# Clock.net
KiCad netlist of a schematic drawn in EAGLE
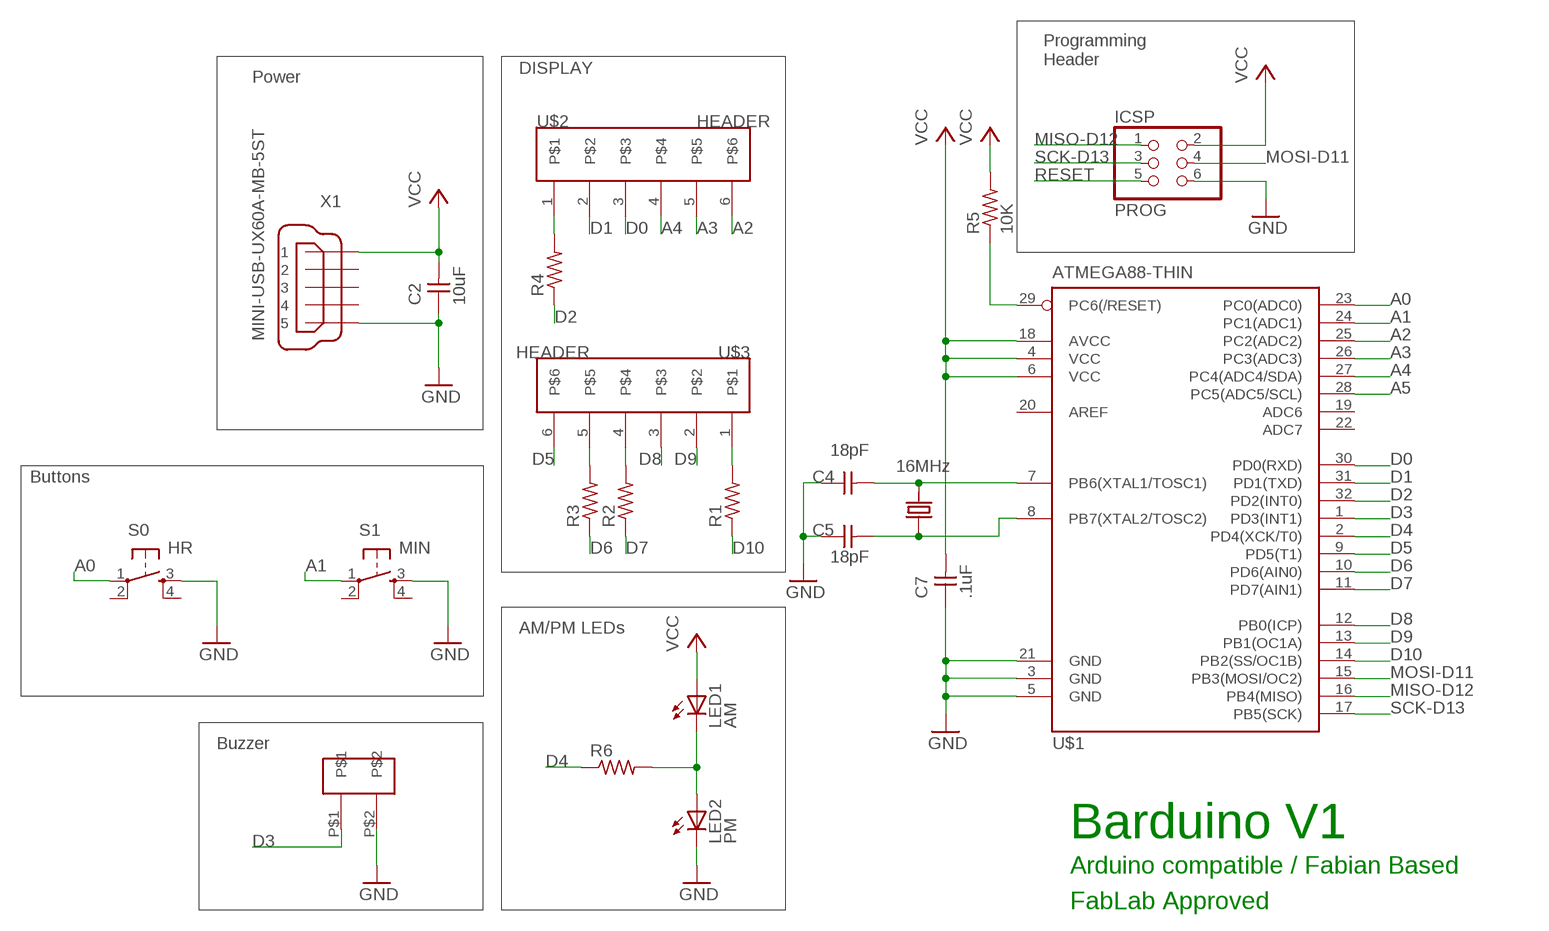
[diagram p0: schematic, sheet 1]

(export (version "E")
  (design (tool "Eeschema 10.0.6"))
  (components
    (comp (ref "C2")
      (value "10uF")
      (footprint "eagle-import:1206")
      (libsource (lib "eagle-import") (part "UNPOLARIZED_CAPACITOR1206"))
    )
    (comp (ref "C4")
      (value "18pF")
      (footprint "eagle-import:1206")
      (libsource (lib "eagle-import") (part "UNPOLARIZED_CAPACITOR1206"))
    )
    (comp (ref "C5")
      (value "18pF")
      (footprint "eagle-import:1206")
      (libsource (lib "eagle-import") (part "UNPOLARIZED_CAPACITOR1206"))
    )
    (comp (ref "C7")
      (value ".1uF")
      (footprint "eagle-import:1206")
      (libsource (lib "eagle-import") (part "UNPOLARIZED_CAPACITOR1206"))
    )
    (comp (ref "ICSP")
      (value "PROG")
      (footprint "eagle-import:2X03SMD")
      (libsource (lib "eagle-import") (part "PINHD-2X3-SMD"))
    )
    (comp (ref "LED1")
      (value "AM")
      (footprint "eagle-import:CHIPLED_1206")
      (libsource (lib "eagle-import") (part "LEDCHIPLED_1206"))
    )
    (comp (ref "LED2")
      (value "PM")
      (footprint "eagle-import:CHIPLED_1206")
      (libsource (lib "eagle-import") (part "LEDCHIPLED_1206"))
    )
    (comp (ref "Q2")
      (value "16MHz")
      (footprint "eagle-import:CS10")
      (libsource (lib "eagle-import") (part "CRYSTALCS10"))
    )
    (comp (ref "R1")
      (value "R-US_R1206")
      (footprint "eagle-import:R1206")
      (libsource (lib "eagle-import") (part "R-US_R1206"))
    )
    (comp (ref "R2")
      (value "R-US_R1206")
      (footprint "eagle-import:R1206")
      (libsource (lib "eagle-import") (part "R-US_R1206"))
    )
    (comp (ref "R3")
      (value "R-US_R1206")
      (footprint "eagle-import:R1206")
      (libsource (lib "eagle-import") (part "R-US_R1206"))
    )
    (comp (ref "R4")
      (value "R-US_R1206")
      (footprint "eagle-import:R1206")
      (libsource (lib "eagle-import") (part "R-US_R1206"))
    )
    (comp (ref "R5")
      (value "10K")
      (footprint "eagle-import:1206")
      (libsource (lib "eagle-import") (part "RESISTOR1206"))
    )
    (comp (ref "R6")
      (value "R-US_R1206")
      (footprint "eagle-import:R1206")
      (libsource (lib "eagle-import") (part "R-US_R1206"))
    )
    (comp (ref "S0")
      (value "HR")
      (footprint "eagle-import:6MM_SWITCH")
      (libsource (lib "eagle-import") (part "6MM_SWITCH6MM_SWITCH"))
    )
    (comp (ref "S1")
      (value "MIN")
      (footprint "eagle-import:6MM_SWITCH")
      (libsource (lib "eagle-import") (part "6MM_SWITCH6MM_SWITCH"))
    )
    (comp (ref "U$1")
      (value "ATMEGA88-THIN")
      (footprint "eagle-import:TQFP32-08THIN")
      (libsource (lib "eagle-import") (part "ATMEGA88-THIN"))
    )
    (comp (ref "U$2")
      (value "HEADER")
      (footprint "eagle-import:HEADER")
      (libsource (lib "eagle-import") (part "HEADER"))
    )
    (comp (ref "U$3")
      (value "HEADER")
      (footprint "eagle-import:HEADER")
      (libsource (lib "eagle-import") (part "HEADER"))
    )
    (comp (ref "U$4")
      (value "BUZZER")
      (footprint "eagle-import:BUZZER")
      (libsource (lib "eagle-import") (part "BUZZER"))
    )
    (comp (ref "X1")
      (value "MINI-USB-UX60A-MB-5ST")
      (footprint "eagle-import:UX60A-MB-5ST")
      (libsource (lib "eagle-import") (part "MINI-USB-UX60A-MB-5ST"))
    )
  )
  (nets
    (net (code "1") (name "/A0") (class "Default")
      (node (ref "S0") (pin "1") (pinfunction "P_1") (pintype "passive"))
      (node (ref "U$1") (pin "23") (pinfunction "PC0(ADC0)_23") (pintype "bidirectional"))
    )
    (net (code "2") (name "/A1") (class "Default")
      (node (ref "S1") (pin "1") (pinfunction "P_1") (pintype "passive"))
      (node (ref "U$1") (pin "24") (pinfunction "PC1(ADC1)_24") (pintype "bidirectional"))
    )
    (net (code "3") (name "/A2") (class "Default")
      (node (ref "U$1") (pin "25") (pinfunction "PC2(ADC2)_25") (pintype "bidirectional"))
      (node (ref "U$2") (pin "6") (pinfunction "P$6_6") (pintype "bidirectional"))
    )
    (net (code "4") (name "/A3") (class "Default")
      (node (ref "U$1") (pin "26") (pinfunction "PC3(ADC3)_26") (pintype "bidirectional"))
      (node (ref "U$2") (pin "5") (pinfunction "P$5_5") (pintype "bidirectional"))
    )
    (net (code "5") (name "/A4") (class "Default")
      (node (ref "U$1") (pin "27") (pinfunction "PC4(ADC4/SDA)_27") (pintype "bidirectional"))
      (node (ref "U$2") (pin "4") (pinfunction "P$4_4") (pintype "bidirectional"))
    )
    (net (code "6") (name "/A5") (class "Default")
      (node (ref "U$1") (pin "28") (pinfunction "PC5(ADC5/SCL)_28") (pintype "bidirectional"))
    )
    (net (code "7") (name "/D0") (class "Default")
      (node (ref "U$1") (pin "30") (pinfunction "PD0(RXD)_30") (pintype "bidirectional"))
      (node (ref "U$2") (pin "3") (pinfunction "P$3_3") (pintype "bidirectional"))
    )
    (net (code "8") (name "/D1") (class "Default")
      (node (ref "U$1") (pin "31") (pinfunction "PD1(TXD)_31") (pintype "bidirectional"))
      (node (ref "U$2") (pin "2") (pinfunction "P$2_2") (pintype "bidirectional"))
    )
    (net (code "9") (name "/D2") (class "Default")
      (node (ref "R4") (pin "1") (pinfunction "1_1") (pintype "passive"))
      (node (ref "U$1") (pin "32") (pinfunction "PD2(INT0)_32") (pintype "bidirectional"))
    )
    (net (code "10") (name "/D3") (class "Default")
      (node (ref "U$1") (pin "1") (pinfunction "PD3(INT1)_1") (pintype "bidirectional"))
      (node (ref "U$4") (pin "P$1") (pinfunction "P$1_P$1") (pintype "bidirectional"))
    )
    (net (code "11") (name "/D4") (class "Default")
      (node (ref "R6") (pin "1") (pinfunction "1_1") (pintype "passive"))
      (node (ref "U$1") (pin "2") (pinfunction "PD4(XCK/T0)_2") (pintype "bidirectional"))
    )
    (net (code "12") (name "/D5") (class "Default")
      (node (ref "U$1") (pin "9") (pinfunction "PD5(T1)_9") (pintype "bidirectional"))
      (node (ref "U$3") (pin "6") (pinfunction "P$6_6") (pintype "bidirectional"))
    )
    (net (code "13") (name "/D6") (class "Default")
      (node (ref "R3") (pin "1") (pinfunction "1_1") (pintype "passive"))
      (node (ref "U$1") (pin "10") (pinfunction "PD6(AIN0)_10") (pintype "bidirectional"))
    )
    (net (code "14") (name "/D7") (class "Default")
      (node (ref "R2") (pin "1") (pinfunction "1_1") (pintype "passive"))
      (node (ref "U$1") (pin "11") (pinfunction "PD7(AIN1)_11") (pintype "bidirectional"))
    )
    (net (code "15") (name "/D8") (class "Default")
      (node (ref "U$1") (pin "12") (pinfunction "PB0(ICP)_12") (pintype "bidirectional"))
      (node (ref "U$3") (pin "3") (pinfunction "P$3_3") (pintype "bidirectional"))
    )
    (net (code "16") (name "/D9") (class "Default")
      (node (ref "U$1") (pin "13") (pinfunction "PB1(OC1A)_13") (pintype "bidirectional"))
      (node (ref "U$3") (pin "2") (pinfunction "P$2_2") (pintype "bidirectional"))
    )
    (net (code "17") (name "/D10") (class "Default")
      (node (ref "R1") (pin "1") (pinfunction "1_1") (pintype "passive"))
      (node (ref "U$1") (pin "14") (pinfunction "PB2(SS/OC1B)_14") (pintype "bidirectional"))
    )
    (net (code "18") (name "/MISO-D12") (class "Default")
      (node (ref "ICSP") (pin "1") (pinfunction "1_1") (pintype "passive"))
      (node (ref "U$1") (pin "16") (pinfunction "PB4(MISO)_16") (pintype "bidirectional"))
    )
    (net (code "19") (name "/MOSI-D11") (class "Default")
      (node (ref "ICSP") (pin "4") (pinfunction "4_4") (pintype "passive"))
      (node (ref "U$1") (pin "15") (pinfunction "PB3(MOSI/OC2)_15") (pintype "bidirectional"))
    )
    (net (code "20") (name "/RESET") (class "Default")
      (node (ref "ICSP") (pin "5") (pinfunction "5_5") (pintype "passive"))
      (node (ref "R5") (pin "1") (pinfunction "1_1") (pintype "passive"))
      (node (ref "U$1") (pin "29") (pinfunction "PC6(/RESET)_29") (pintype "bidirectional"))
    )
    (net (code "21") (name "/SCK-D13") (class "Default")
      (node (ref "ICSP") (pin "3") (pinfunction "3_3") (pintype "passive"))
      (node (ref "U$1") (pin "17") (pinfunction "PB5(SCK)_17") (pintype "bidirectional"))
    )
    (net (code "22") (name "GND") (class "Default")
      (node (ref "C2") (pin "1") (pinfunction "1_1") (pintype "passive"))
      (node (ref "C4") (pin "1") (pinfunction "1_1") (pintype "passive"))
      (node (ref "C5") (pin "1") (pinfunction "1_1") (pintype "passive"))
      (node (ref "C7") (pin "1") (pinfunction "1_1") (pintype "passive"))
      (node (ref "ICSP") (pin "6") (pinfunction "6_6") (pintype "passive"))
      (node (ref "LED2") (pin "C") (pinfunction "C_C") (pintype "passive"))
      (node (ref "S0") (pin "3") (pinfunction "S_3") (pintype "passive"))
      (node (ref "S1") (pin "3") (pinfunction "S_3") (pintype "passive"))
      (node (ref "U$1") (pin "21") (pinfunction "GND_21") (pintype "power_in"))
      (node (ref "U$1") (pin "3") (pinfunction "GND_3") (pintype "power_in"))
      (node (ref "U$1") (pin "5") (pinfunction "GND_5") (pintype "power_in"))
      (node (ref "U$4") (pin "P$2") (pinfunction "P$2_P$2") (pintype "bidirectional"))
      (node (ref "X1") (pin "5") (pinfunction "5_5") (pintype "input"))
    )
    (net (code "23") (name "Net-(LED1-PadC)") (class "Default")
      (node (ref "LED1") (pin "C") (pinfunction "C_C") (pintype "passive"))
      (node (ref "LED2") (pin "A") (pinfunction "A_A") (pintype "passive"))
      (node (ref "R6") (pin "2") (pinfunction "2_2") (pintype "passive"))
    )
    (net (code "24") (name "Net-(Q2-1)") (class "Default")
      (node (ref "C5") (pin "2") (pinfunction "2_2") (pintype "passive"))
      (node (ref "Q2") (pin "P$1") (pinfunction "1_P$1") (pintype "passive"))
      (node (ref "U$1") (pin "8") (pinfunction "PB7(XTAL2/TOSC2)_8") (pintype "bidirectional"))
    )
    (net (code "25") (name "Net-(Q2-2)") (class "Default")
      (node (ref "C4") (pin "2") (pinfunction "2_2") (pintype "passive"))
      (node (ref "Q2") (pin "P$2") (pinfunction "2_P$2") (pintype "passive"))
      (node (ref "U$1") (pin "7") (pinfunction "PB6(XTAL1/TOSC1)_7") (pintype "bidirectional"))
    )
    (net (code "26") (name "Net-(U$2-P$1)") (class "Default")
      (node (ref "R4") (pin "2") (pinfunction "2_2") (pintype "passive"))
      (node (ref "U$2") (pin "1") (pinfunction "P$1_1") (pintype "bidirectional"))
    )
    (net (code "27") (name "Net-(U$3-P$1)") (class "Default")
      (node (ref "R1") (pin "2") (pinfunction "2_2") (pintype "passive"))
      (node (ref "U$3") (pin "1") (pinfunction "P$1_1") (pintype "bidirectional"))
    )
    (net (code "28") (name "Net-(U$3-P$4)") (class "Default")
      (node (ref "R2") (pin "2") (pinfunction "2_2") (pintype "passive"))
      (node (ref "U$3") (pin "4") (pinfunction "P$4_4") (pintype "bidirectional"))
    )
    (net (code "29") (name "Net-(U$3-P$5)") (class "Default")
      (node (ref "R3") (pin "2") (pinfunction "2_2") (pintype "passive"))
      (node (ref "U$3") (pin "5") (pinfunction "P$5_5") (pintype "bidirectional"))
    )
    (net (code "30") (name "VCC") (class "Default")
      (node (ref "C2") (pin "2") (pinfunction "2_2") (pintype "passive"))
      (node (ref "C7") (pin "2") (pinfunction "2_2") (pintype "passive"))
      (node (ref "ICSP") (pin "2") (pinfunction "2_2") (pintype "passive"))
      (node (ref "LED1") (pin "A") (pinfunction "A_A") (pintype "passive"))
      (node (ref "R5") (pin "2") (pinfunction "2_2") (pintype "passive"))
      (node (ref "U$1") (pin "18") (pinfunction "AVCC_18") (pintype "power_in"))
      (node (ref "U$1") (pin "4") (pinfunction "VCC_4") (pintype "power_in"))
      (node (ref "U$1") (pin "6") (pinfunction "VCC_6") (pintype "power_in"))
      (node (ref "X1") (pin "1") (pinfunction "1_1") (pintype "input"))
    )
    (net (code "31") (name "unconnected-(S0-P1-Pad2)") (class "Default")
      (node (ref "S0") (pin "2") (pinfunction "P1_2") (pintype "passive"))
    )
    (net (code "32") (name "unconnected-(S0-S1-Pad4)") (class "Default")
      (node (ref "S0") (pin "4") (pinfunction "S1_4") (pintype "passive"))
    )
    (net (code "33") (name "unconnected-(S1-P1-Pad2)") (class "Default")
      (node (ref "S1") (pin "2") (pinfunction "P1_2") (pintype "passive"))
    )
    (net (code "34") (name "unconnected-(S1-S1-Pad4)") (class "Default")
      (node (ref "S1") (pin "4") (pinfunction "S1_4") (pintype "passive"))
    )
    (net (code "35") (name "unconnected-(U$1-ADC6-Pad19)") (class "Default")
      (node (ref "U$1") (pin "19") (pinfunction "ADC6_19") (pintype "bidirectional"))
    )
    (net (code "36") (name "unconnected-(U$1-ADC7-Pad22)") (class "Default")
      (node (ref "U$1") (pin "22") (pinfunction "ADC7_22") (pintype "bidirectional"))
    )
    (net (code "37") (name "unconnected-(U$1-AREF-Pad20)") (class "Default")
      (node (ref "U$1") (pin "20") (pinfunction "AREF_20") (pintype "passive"))
    )
    (net (code "38") (name "unconnected-(X1-Pad2)") (class "Default")
      (node (ref "X1") (pin "2") (pinfunction "2_2") (pintype "input"))
    )
    (net (code "39") (name "unconnected-(X1-Pad3)") (class "Default")
      (node (ref "X1") (pin "3") (pinfunction "3_3") (pintype "input"))
    )
    (net (code "40") (name "unconnected-(X1-Pad4)") (class "Default")
      (node (ref "X1") (pin "4") (pinfunction "4_4") (pintype "input"))
    )
  )
)
